# CMoy_-_OPA1622.net
KiCad netlist of a schematic drawn in EAGLE
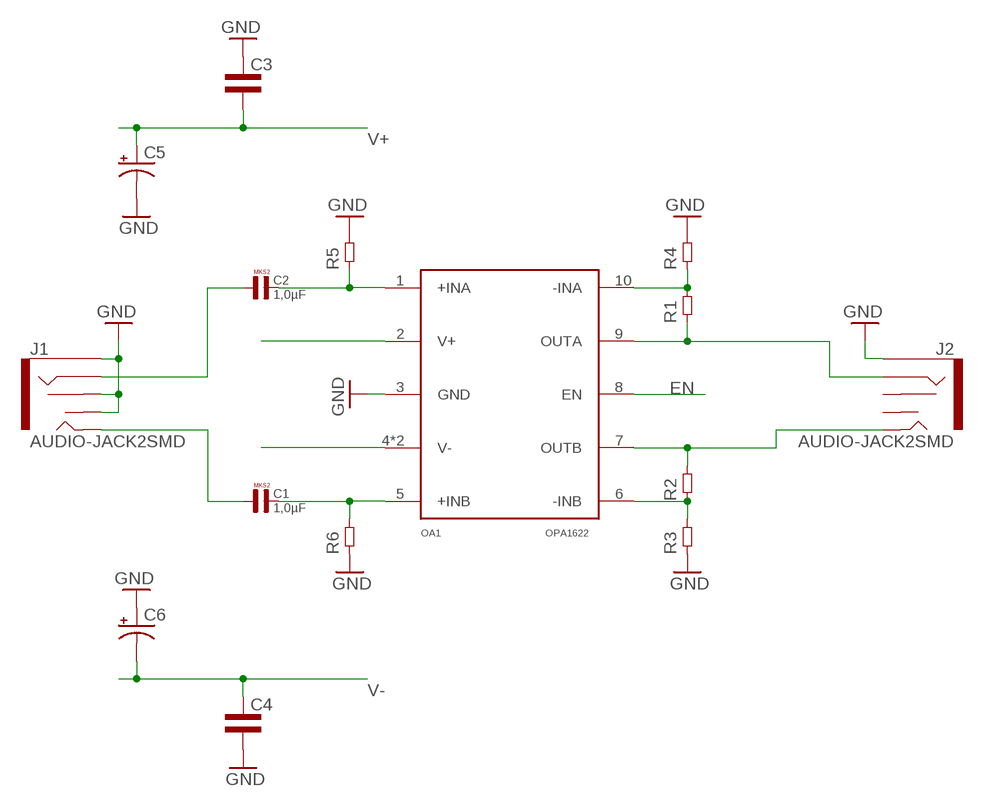
[diagram p0: schematic, sheet 1]

(export (version "E")
  (design (tool "Eeschema 10.0.6"))
  (components
    (comp (ref "C1")
      (value "1,0µF")
      (footprint "eagle-import:R5B5")
      (libsource (lib "eagle-import") (part "1,0µF"))
    )
    (comp (ref "C2")
      (value "1,0µF")
      (footprint "eagle-import:R5B5")
      (libsource (lib "eagle-import") (part "1,0µF"))
    )
    (comp (ref "C3")
      (value "CAP0402L3")
      (footprint "eagle-import:0402L3")
      (libsource (lib "eagle-import") (part "CAP0402L3"))
    )
    (comp (ref "C4")
      (value "CAP0402L3")
      (footprint "eagle-import:0402L3")
      (libsource (lib "eagle-import") (part "CAP0402L3"))
    )
    (comp (ref "C5")
      (value "CPOL-USE5-10.5")
      (footprint "eagle-import:E5-10,5")
      (libsource (lib "eagle-import") (part "CPOL-USE5-10.5"))
    )
    (comp (ref "C6")
      (value "CPOL-USE5-10.5")
      (footprint "eagle-import:E5-10,5")
      (libsource (lib "eagle-import") (part "CPOL-USE5-10.5"))
    )
    (comp (ref "J1")
      (value "AUDIO-JACK2SMD")
      (footprint "eagle-import:AUDIO-JACK-3.5MM-SMD")
      (libsource (lib "eagle-import") (part "AUDIO-JACK2SMD"))
    )
    (comp (ref "J2")
      (value "AUDIO-JACK2SMD")
      (footprint "eagle-import:AUDIO-JACK-3.5MM-SMD")
      (libsource (lib "eagle-import") (part "AUDIO-JACK2SMD"))
    )
    (comp (ref "OA1")
      (value "OPA1622")
      (footprint "eagle-import:S-PVSON-N10")
      (libsource (lib "eagle-import") (part "OPA1622"))
    )
    (comp (ref "R1")
      (value "RES0402L3")
      (footprint "eagle-import:0402L3")
      (libsource (lib "eagle-import") (part "RES0402L3"))
    )
    (comp (ref "R2")
      (value "RES0402L3")
      (footprint "eagle-import:0402L3")
      (libsource (lib "eagle-import") (part "RES0402L3"))
    )
    (comp (ref "R3")
      (value "RES0402L3")
      (footprint "eagle-import:0402L3")
      (libsource (lib "eagle-import") (part "RES0402L3"))
    )
    (comp (ref "R4")
      (value "RES0402L3")
      (footprint "eagle-import:0402L3")
      (libsource (lib "eagle-import") (part "RES0402L3"))
    )
    (comp (ref "R5")
      (value "RES0402L3")
      (footprint "eagle-import:0402L3")
      (libsource (lib "eagle-import") (part "RES0402L3"))
    )
    (comp (ref "R6")
      (value "RES0402L3")
      (footprint "eagle-import:0402L3")
      (libsource (lib "eagle-import") (part "RES0402L3"))
    )
  )
  (nets
    (net (code "1") (name "/EN") (class "Default")
      (node (ref "OA1") (pin "8") (pinfunction "EN_8") (pintype "bidirectional"))
    )
    (net (code "2") (name "/V+") (class "Default")
      (node (ref "C3") (pin "P$2") (pinfunction "2_P$2") (pintype "bidirectional"))
      (node (ref "C5") (pin "+") (pinfunction "+_+") (pintype "passive"))
      (node (ref "OA1") (pin "2") (pinfunction "V+_2") (pintype "bidirectional"))
    )
    (net (code "3") (name "/V-") (class "Default")
      (node (ref "C4") (pin "P$1") (pinfunction "1_P$1") (pintype "bidirectional"))
      (node (ref "C6") (pin "-") (pinfunction "-_-") (pintype "passive"))
      (node (ref "OA1") (pin "4") (pinfunction "V-_4") (pintype "bidirectional"))
      (node (ref "OA1") (pin "TP") (pinfunction "V-_TP") (pintype "bidirectional"))
    )
    (net (code "4") (name "GND") (class "Default")
      (node (ref "C3") (pin "P$1") (pinfunction "1_P$1") (pintype "bidirectional"))
      (node (ref "C4") (pin "P$2") (pinfunction "2_P$2") (pintype "bidirectional"))
      (node (ref "C5") (pin "-") (pinfunction "-_-") (pintype "passive"))
      (node (ref "C6") (pin "+") (pinfunction "+_+") (pintype "passive"))
      (node (ref "J1") (pin "RSH") (pinfunction "RSH_RSH") (pintype "bidirectional"))
      (node (ref "J1") (pin "SLEEVE") (pinfunction "SLEEVE_SLEEVE") (pintype "bidirectional"))
      (node (ref "J1") (pin "TSH") (pinfunction "TSH_TSH") (pintype "bidirectional"))
      (node (ref "J2") (pin "SLEEVE") (pinfunction "SLEEVE_SLEEVE") (pintype "bidirectional"))
      (node (ref "OA1") (pin "3") (pinfunction "GND_3") (pintype "bidirectional"))
      (node (ref "R3") (pin "P$1") (pinfunction "1_P$1") (pintype "bidirectional"))
      (node (ref "R4") (pin "P$2") (pinfunction "2_P$2") (pintype "bidirectional"))
      (node (ref "R5") (pin "P$2") (pinfunction "2_P$2") (pintype "bidirectional"))
      (node (ref "R6") (pin "P$1") (pinfunction "1_P$1") (pintype "bidirectional"))
    )
    (net (code "5") (name "Net-(C1-Pad1)") (class "Default")
      (node (ref "C1") (pin "1") (pinfunction "1_1") (pintype "passive"))
      (node (ref "J1") (pin "TIP") (pinfunction "TIP_TIP") (pintype "bidirectional"))
    )
    (net (code "6") (name "Net-(C2-Pad1)") (class "Default")
      (node (ref "C2") (pin "1") (pinfunction "1_1") (pintype "passive"))
      (node (ref "J1") (pin "RING") (pinfunction "RING_RING") (pintype "bidirectional"))
    )
    (net (code "7") (name "Net-(OA1-+INA)") (class "Default")
      (node (ref "C2") (pin "2") (pinfunction "2_2") (pintype "passive"))
      (node (ref "OA1") (pin "1") (pinfunction "+INA_1") (pintype "bidirectional"))
      (node (ref "R5") (pin "P$1") (pinfunction "1_P$1") (pintype "bidirectional"))
    )
    (net (code "8") (name "Net-(OA1-+INB)") (class "Default")
      (node (ref "C1") (pin "2") (pinfunction "2_2") (pintype "passive"))
      (node (ref "OA1") (pin "5") (pinfunction "+INB_5") (pintype "bidirectional"))
      (node (ref "R6") (pin "P$2") (pinfunction "2_P$2") (pintype "bidirectional"))
    )
    (net (code "9") (name "Net-(OA1--INA)") (class "Default")
      (node (ref "OA1") (pin "10") (pinfunction "-INA_10") (pintype "bidirectional"))
      (node (ref "R1") (pin "P$2") (pinfunction "2_P$2") (pintype "bidirectional"))
      (node (ref "R4") (pin "P$1") (pinfunction "1_P$1") (pintype "bidirectional"))
    )
    (net (code "10") (name "Net-(OA1--INB)") (class "Default")
      (node (ref "OA1") (pin "6") (pinfunction "-INB_6") (pintype "bidirectional"))
      (node (ref "R2") (pin "P$1") (pinfunction "1_P$1") (pintype "bidirectional"))
      (node (ref "R3") (pin "P$2") (pinfunction "2_P$2") (pintype "bidirectional"))
    )
    (net (code "11") (name "Net-(OA1-OUTA)") (class "Default")
      (node (ref "J2") (pin "RING") (pinfunction "RING_RING") (pintype "bidirectional"))
      (node (ref "OA1") (pin "9") (pinfunction "OUTA_9") (pintype "bidirectional"))
      (node (ref "R1") (pin "P$1") (pinfunction "1_P$1") (pintype "bidirectional"))
    )
    (net (code "12") (name "Net-(OA1-OUTB)") (class "Default")
      (node (ref "J2") (pin "TIP") (pinfunction "TIP_TIP") (pintype "bidirectional"))
      (node (ref "OA1") (pin "7") (pinfunction "OUTB_7") (pintype "bidirectional"))
      (node (ref "R2") (pin "P$2") (pinfunction "2_P$2") (pintype "bidirectional"))
    )
    (net (code "13") (name "unconnected-(J2-PadRSH)") (class "Default")
      (node (ref "J2") (pin "RSH") (pinfunction "RSH_RSH") (pintype "bidirectional"))
    )
    (net (code "14") (name "unconnected-(J2-PadTSH)") (class "Default")
      (node (ref "J2") (pin "TSH") (pinfunction "TSH_TSH") (pintype "bidirectional"))
    )
  )
)
